# FPGA_Bypass_2V5.net
KiCad netlist of a schematic drawn in Altium Designer
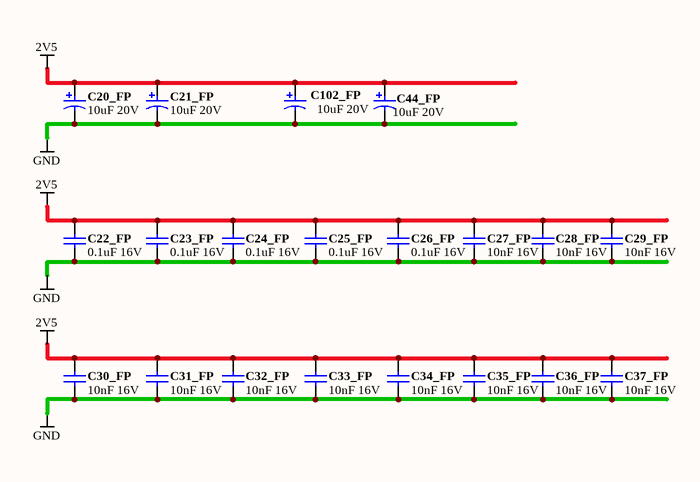
[diagram p0: FPGA_Bypass_2V5.SCHDOC]

(export (version "E")
  (design (tool "Eeschema 10.0.6"))
  (components
    (comp (ref "C20_FP")
      (value "10uF 20V")
      (footprint "CAPC3528-STAR")
      (description "Capacitor, Tantalum, 10uF 10% 20V MCCT-B (3528)")
      (fields (field (name "TOLERANCE") "10 %"))
      (libsource (lib "altium-import") (part "root_0_CAP-P_"))
    )
    (comp (ref "C21_FP")
      (value "10uF 20V")
      (footprint "CAPC3528-STAR")
      (description "Capacitor, Tantalum, 10uF 10% 20V MCCT-B (3528)")
      (fields (field (name "TOLERANCE") "10 %"))
      (libsource (lib "altium-import") (part "root_0_CAP-P_"))
    )
    (comp (ref "C22_FP")
      (value "0.1uF 16V")
      (footprint "CAPC1005-STAR")
      (description "Capacitor, Ceramic, 0.1uF 10% 16V 0402 (1005) X7R")
      (fields (field (name "TOLERANCE") "10 %"))
      (libsource (lib "altium-import") (part "root_0_mirrored_CAP-NP_"))
    )
    (comp (ref "C23_FP")
      (value "0.1uF 16V")
      (footprint "CAPC1005-STAR")
      (description "Capacitor, Ceramic, 0.1uF 10% 16V 0402 (1005) X7R")
      (fields (field (name "TOLERANCE") "10 %"))
      (libsource (lib "altium-import") (part "root_0_mirrored_CAP-NP_"))
    )
    (comp (ref "C24_FP")
      (value "0.1uF 16V")
      (footprint "CAPC1005-STAR")
      (description "Capacitor, Ceramic, 0.1uF 10% 16V 0402 (1005) X7R")
      (fields (field (name "TOLERANCE") "10 %"))
      (libsource (lib "altium-import") (part "root_0_mirrored_CAP-NP_"))
    )
    (comp (ref "C25_FP")
      (value "0.1uF 16V")
      (footprint "CAPC1005-STAR")
      (description "Capacitor, Ceramic, 0.1uF 10% 16V 0402 (1005) X7R")
      (fields (field (name "TOLERANCE") "10 %"))
      (libsource (lib "altium-import") (part "root_0_mirrored_CAP-NP_"))
    )
    (comp (ref "C26_FP")
      (value "0.1uF 16V")
      (footprint "CAPC1005-STAR")
      (description "Capacitor, Ceramic, 0.1uF 10% 16V 0402 (1005) X7R")
      (fields (field (name "TOLERANCE") "10 %"))
      (libsource (lib "altium-import") (part "root_0_mirrored_CAP-NP_"))
    )
    (comp (ref "C27_FP")
      (value "10nF 16V")
      (footprint "CAPC1005-STAR")
      (description "Capacitor, Ceramic, 10nF 10% 16V 0402 (1005) X7R")
      (fields (field (name "TOLERANCE") "10 %"))
      (libsource (lib "altium-import") (part "root_0_CAP-NP_"))
    )
    (comp (ref "C28_FP")
      (value "10nF 16V")
      (footprint "CAPC1005-STAR")
      (description "Capacitor, Ceramic, 10nF 10% 16V 0402 (1005) X7R")
      (fields (field (name "TOLERANCE") "10 %"))
      (libsource (lib "altium-import") (part "root_0_CAP-NP_"))
    )
    (comp (ref "C29_FP")
      (value "10nF 16V")
      (footprint "CAPC1005-STAR")
      (description "Capacitor, Ceramic, 10nF 10% 16V 0402 (1005) X7R")
      (fields (field (name "TOLERANCE") "10 %"))
      (libsource (lib "altium-import") (part "root_0_CAP-NP_"))
    )
    (comp (ref "C30_FP")
      (value "10nF 16V")
      (footprint "CAPC1005-STAR")
      (description "Capacitor, Ceramic, 10nF 10% 16V 0402 (1005) X7R")
      (fields (field (name "TOLERANCE") "10 %"))
      (libsource (lib "altium-import") (part "root_0_CAP-NP_"))
    )
    (comp (ref "C31_FP")
      (value "10nF 16V")
      (footprint "CAPC1005-STAR")
      (description "Capacitor, Ceramic, 10nF 10% 16V 0402 (1005) X7R")
      (fields (field (name "TOLERANCE") "10 %"))
      (libsource (lib "altium-import") (part "root_0_CAP-NP_"))
    )
    (comp (ref "C32_FP")
      (value "10nF 16V")
      (footprint "CAPC1005-STAR")
      (description "Capacitor, Ceramic, 10nF 10% 16V 0402 (1005) X7R")
      (fields (field (name "TOLERANCE") "10 %"))
      (libsource (lib "altium-import") (part "root_0_CAP-NP_"))
    )
    (comp (ref "C33_FP")
      (value "10nF 16V")
      (footprint "CAPC1005-STAR")
      (description "Capacitor, Ceramic, 10nF 10% 16V 0402 (1005) X7R")
      (fields (field (name "TOLERANCE") "10 %"))
      (libsource (lib "altium-import") (part "root_0_CAP-NP_"))
    )
    (comp (ref "C34_FP")
      (value "10nF 16V")
      (footprint "CAPC1005-STAR")
      (description "Capacitor, Ceramic, 10nF 10% 16V 0402 (1005) X7R")
      (fields (field (name "TOLERANCE") "10 %"))
      (libsource (lib "altium-import") (part "root_0_CAP-NP_"))
    )
    (comp (ref "C35_FP")
      (value "10nF 16V")
      (footprint "CAPC1005-STAR")
      (description "Capacitor, Ceramic, 10nF 10% 16V 0402 (1005) X7R")
      (fields (field (name "TOLERANCE") "10 %"))
      (libsource (lib "altium-import") (part "root_0_CAP-NP_"))
    )
    (comp (ref "C36_FP")
      (value "10nF 16V")
      (footprint "CAPC1005-STAR")
      (description "Capacitor, Ceramic, 10nF 10% 16V 0402 (1005) X7R")
      (fields (field (name "TOLERANCE") "10 %"))
      (libsource (lib "altium-import") (part "root_0_CAP-NP_"))
    )
    (comp (ref "C37_FP")
      (value "10nF 16V")
      (footprint "CAPC1005-STAR")
      (description "Capacitor, Ceramic, 10nF 10% 16V 0402 (1005) X7R")
      (fields (field (name "TOLERANCE") "10 %"))
      (libsource (lib "altium-import") (part "root_0_CAP-NP_"))
    )
    (comp (ref "C44_FP")
      (value "10uF 20V")
      (footprint "CAPC3528-STAR")
      (description "Capacitor, Tantalum, 10uF 10% 20V MCCT-B (3528)")
      (fields (field (name "TOLERANCE") "10 %"))
      (libsource (lib "altium-import") (part "root_0_CAP-P_"))
    )
    (comp (ref "C102_FP")
      (value "10uF 20V")
      (footprint "CAPC3528-STAR")
      (description "Capacitor, Tantalum, 10uF 10% 20V MCCT-B (3528)")
      (fields (field (name "TOLERANCE") "10 %"))
      (libsource (lib "altium-import") (part "root_0_CAP-P_"))
    )
  )
  (nets
    (net (code "1") (name "2V5") (class "Default")
      (node (ref "C102_FP") (pin "1") (pinfunction "1_1") (pintype "passive"))
      (node (ref "C20_FP") (pin "1") (pinfunction "1_1") (pintype "passive"))
      (node (ref "C21_FP") (pin "1") (pinfunction "1_1") (pintype "passive"))
      (node (ref "C22_FP") (pin "1") (pinfunction "1_1") (pintype "passive"))
      (node (ref "C23_FP") (pin "1") (pinfunction "1_1") (pintype "passive"))
      (node (ref "C24_FP") (pin "1") (pinfunction "1_1") (pintype "passive"))
      (node (ref "C25_FP") (pin "1") (pinfunction "1_1") (pintype "passive"))
      (node (ref "C26_FP") (pin "1") (pinfunction "1_1") (pintype "passive"))
      (node (ref "C27_FP") (pin "1") (pinfunction "1_1") (pintype "passive"))
      (node (ref "C28_FP") (pin "1") (pinfunction "1_1") (pintype "passive"))
      (node (ref "C29_FP") (pin "1") (pinfunction "1_1") (pintype "passive"))
      (node (ref "C30_FP") (pin "1") (pinfunction "1_1") (pintype "passive"))
      (node (ref "C31_FP") (pin "1") (pinfunction "1_1") (pintype "passive"))
      (node (ref "C32_FP") (pin "1") (pinfunction "1_1") (pintype "passive"))
      (node (ref "C33_FP") (pin "1") (pinfunction "1_1") (pintype "passive"))
      (node (ref "C34_FP") (pin "1") (pinfunction "1_1") (pintype "passive"))
      (node (ref "C35_FP") (pin "1") (pinfunction "1_1") (pintype "passive"))
      (node (ref "C36_FP") (pin "1") (pinfunction "1_1") (pintype "passive"))
      (node (ref "C37_FP") (pin "1") (pinfunction "1_1") (pintype "passive"))
      (node (ref "C44_FP") (pin "1") (pinfunction "1_1") (pintype "passive"))
    )
    (net (code "2") (name "GND") (class "Default")
      (node (ref "C102_FP") (pin "2") (pinfunction "2_2") (pintype "passive"))
      (node (ref "C20_FP") (pin "2") (pinfunction "2_2") (pintype "passive"))
      (node (ref "C21_FP") (pin "2") (pinfunction "2_2") (pintype "passive"))
      (node (ref "C22_FP") (pin "2") (pinfunction "2_2") (pintype "passive"))
      (node (ref "C23_FP") (pin "2") (pinfunction "2_2") (pintype "passive"))
      (node (ref "C24_FP") (pin "2") (pinfunction "2_2") (pintype "passive"))
      (node (ref "C25_FP") (pin "2") (pinfunction "2_2") (pintype "passive"))
      (node (ref "C26_FP") (pin "2") (pinfunction "2_2") (pintype "passive"))
      (node (ref "C27_FP") (pin "2") (pinfunction "2_2") (pintype "passive"))
      (node (ref "C28_FP") (pin "2") (pinfunction "2_2") (pintype "passive"))
      (node (ref "C29_FP") (pin "2") (pinfunction "2_2") (pintype "passive"))
      (node (ref "C30_FP") (pin "2") (pinfunction "2_2") (pintype "passive"))
      (node (ref "C31_FP") (pin "2") (pinfunction "2_2") (pintype "passive"))
      (node (ref "C32_FP") (pin "2") (pinfunction "2_2") (pintype "passive"))
      (node (ref "C33_FP") (pin "2") (pinfunction "2_2") (pintype "passive"))
      (node (ref "C34_FP") (pin "2") (pinfunction "2_2") (pintype "passive"))
      (node (ref "C35_FP") (pin "2") (pinfunction "2_2") (pintype "passive"))
      (node (ref "C36_FP") (pin "2") (pinfunction "2_2") (pintype "passive"))
      (node (ref "C37_FP") (pin "2") (pinfunction "2_2") (pintype "passive"))
      (node (ref "C44_FP") (pin "2") (pinfunction "2_2") (pintype "passive"))
    )
  )
)
